# dedo_rev_1_0.net
KiCad netlist of a schematic drawn in EAGLE
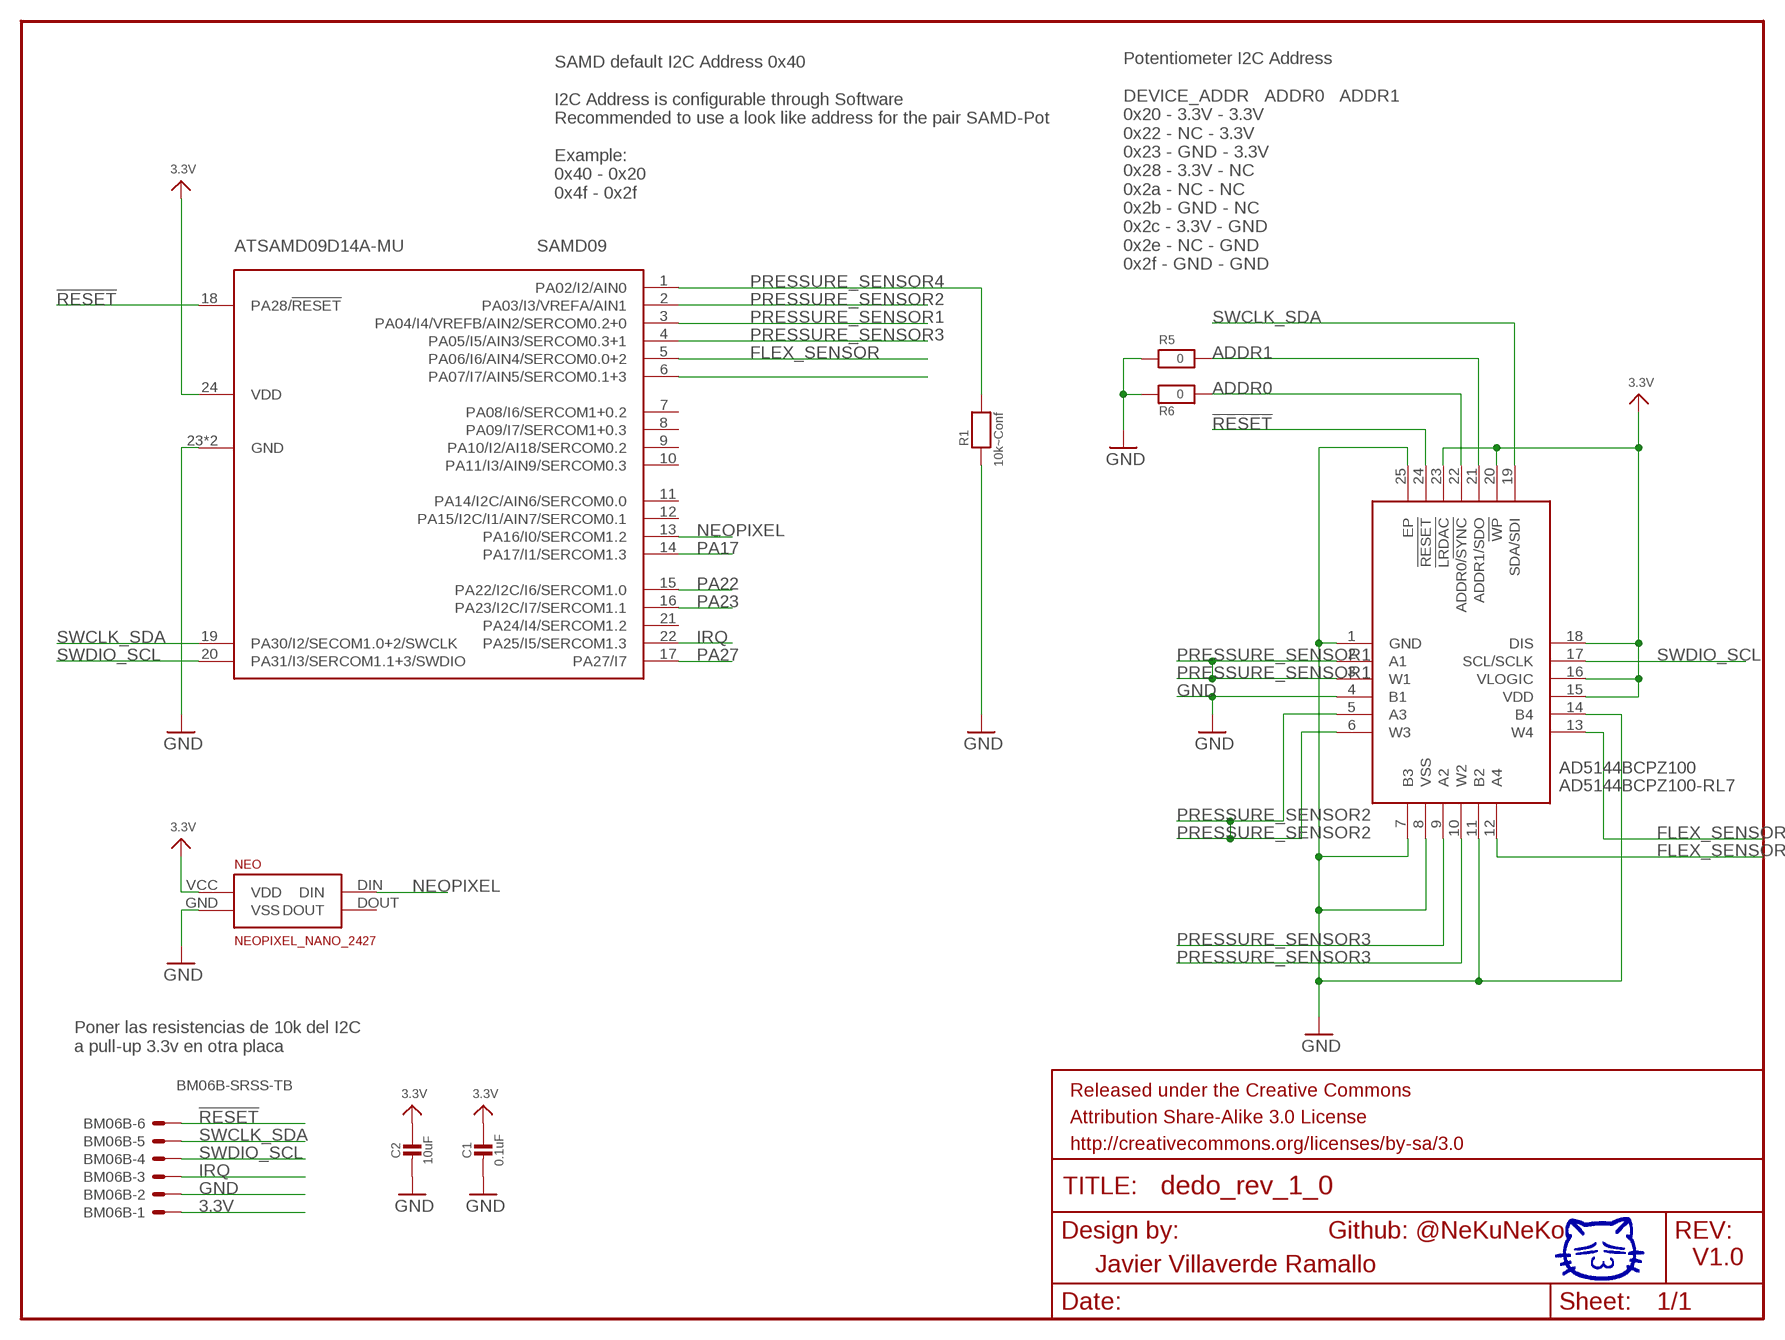
[diagram p0: schematic, sheet 1]

(export (version "E")
  (design (tool "Eeschema 10.0.6"))
  (components
    (comp (ref "AD5144BCPZ100")
      (value "AD5144BCPZ100-RL7")
      (footprint "eagle-import:QFN50P400X400X80-25N")
      (fields (field (name "MOUSER_PART_NUMBER") "584-AD5144BCPZ100-R7"))
      (libsource (lib "eagle-import") (part "AD5144BCPZ100-RL7"))
    )
    (comp (ref "BM06B")
      (value "BM06B-SRSS-TB")
      (footprint "eagle-import:BM06B-SRSS-TB")
      (libsource (lib "eagle-import") (part "?M06B-SRSS-TBB"))
    )
    (comp (ref "C1")
      (value "0.1uF")
      (footprint "eagle-import:0402")
      (libsource (lib "eagle-import") (part "CAP_CERAMIC0402"))
    )
    (comp (ref "C2")
      (value "10uF")
      (footprint "eagle-import:0402")
      (libsource (lib "eagle-import") (part "CAP_CERAMIC0402"))
    )
    (comp (ref "FRAME1")
      (value "FRAME-LETTER")
      (footprint "eagle-import:CREATIVE_COMMONS")
      (libsource (lib "eagle-import") (part "FRAME-LETTER"))
    )
    (comp (ref "FRAME2")
      (value "FRAME-LETTER")
      (footprint "eagle-import:CREATIVE_COMMONS")
      (libsource (lib "eagle-import") (part "FRAME-LETTER"))
    )
    (comp (ref "NEO")
      (value "NEOPIXEL_NANO_2427")
      (footprint "eagle-import:SK6805-2427")
      (libsource (lib "eagle-import") (part "NEOPIXEL_NANO_2427"))
    )
    (comp (ref "R1")
      (value "10k~Conf")
      (footprint "eagle-import:_0402")
      (libsource (lib "eagle-import") (part "RESISTOR_0402"))
    )
    (comp (ref "R5")
      (value "0")
      (footprint "eagle-import:_0402")
      (libsource (lib "eagle-import") (part "RESISTOR_0402"))
    )
    (comp (ref "R6")
      (value "0")
      (footprint "eagle-import:_0402")
      (libsource (lib "eagle-import") (part "RESISTOR_0402"))
    )
    (comp (ref "SAMD09")
      (value "ATSAMD09D14A-MU")
      (footprint "eagle-import:QFN24_4MM")
      (libsource (lib "eagle-import") (part "ATSAMD09D14A-MU"))
    )
  )
  (nets
    (net (code "1") (name "/ADDR0") (class "Default")
      (node (ref "AD5144BCPZ100") (pin "22") (pinfunction "ADDR0/~{SYNC}_22") (pintype "bidirectional"))
      (node (ref "R6") (pin "2") (pinfunction "2_2") (pintype "passive"))
    )
    (net (code "2") (name "/ADDR1") (class "Default")
      (node (ref "AD5144BCPZ100") (pin "21") (pinfunction "ADDR1/SDO_21") (pintype "bidirectional"))
      (node (ref "R5") (pin "2") (pinfunction "2_2") (pintype "passive"))
    )
    (net (code "3") (name "/FLEX_SENSOR") (class "Default")
      (node (ref "AD5144BCPZ100") (pin "12") (pinfunction "A4_12") (pintype "bidirectional"))
      (node (ref "AD5144BCPZ100") (pin "13") (pinfunction "W4_13") (pintype "bidirectional"))
      (node (ref "SAMD09") (pin "5") (pinfunction "PA06/I6/AIN4/SERCOM0.0+2_5") (pintype "bidirectional"))
    )
    (net (code "4") (name "/IRQ") (class "Default")
      (node (ref "BM06B") (pin "3") (pinfunction "S_3") (pintype "passive"))
      (node (ref "SAMD09") (pin "22") (pinfunction "PA25/I5/SERCOM1.3_22") (pintype "bidirectional"))
    )
    (net (code "5") (name "/NEOPIXEL") (class "Default")
      (node (ref "NEO") (pin "DIN") (pinfunction "DIN_DIN") (pintype "bidirectional"))
      (node (ref "SAMD09") (pin "13") (pinfunction "PA16/I0/SERCOM1.2_13") (pintype "bidirectional"))
    )
    (net (code "6") (name "/PA17") (class "Default")
      (node (ref "SAMD09") (pin "14") (pinfunction "PA17/I1/SERCOM1.3_14") (pintype "bidirectional"))
    )
    (net (code "7") (name "/PA22") (class "Default")
      (node (ref "SAMD09") (pin "15") (pinfunction "PA22/I2C/I6/SERCOM1.0_15") (pintype "bidirectional"))
    )
    (net (code "8") (name "/PA23") (class "Default")
      (node (ref "SAMD09") (pin "16") (pinfunction "PA23/I2C/I7/SERCOM1.1_16") (pintype "bidirectional"))
    )
    (net (code "9") (name "/PA27") (class "Default")
      (node (ref "SAMD09") (pin "17") (pinfunction "PA27/I7_17") (pintype "bidirectional"))
    )
    (net (code "10") (name "/PRESSURE_SENSOR1") (class "Default")
      (node (ref "AD5144BCPZ100") (pin "2") (pinfunction "A1_2") (pintype "bidirectional"))
      (node (ref "AD5144BCPZ100") (pin "3") (pinfunction "W1_3") (pintype "bidirectional"))
      (node (ref "SAMD09") (pin "3") (pinfunction "PA04/I4/VREFB/AIN2/SERCOM0.2+0_3") (pintype "bidirectional"))
    )
    (net (code "11") (name "/PRESSURE_SENSOR2") (class "Default")
      (node (ref "AD5144BCPZ100") (pin "5") (pinfunction "A3_5") (pintype "bidirectional"))
      (node (ref "AD5144BCPZ100") (pin "6") (pinfunction "W3_6") (pintype "bidirectional"))
      (node (ref "SAMD09") (pin "2") (pinfunction "PA03/I3/VREFA/AIN1_2") (pintype "bidirectional"))
    )
    (net (code "12") (name "/PRESSURE_SENSOR3") (class "Default")
      (node (ref "AD5144BCPZ100") (pin "10") (pinfunction "W2_10") (pintype "bidirectional"))
      (node (ref "AD5144BCPZ100") (pin "9") (pinfunction "A2_9") (pintype "bidirectional"))
      (node (ref "SAMD09") (pin "4") (pinfunction "PA05/I5/AIN3/SERCOM0.3+1_4") (pintype "bidirectional"))
    )
    (net (code "13") (name "/PRESSURE_SENSOR4") (class "Default")
      (node (ref "R1") (pin "1") (pinfunction "1_1") (pintype "passive"))
      (node (ref "SAMD09") (pin "1") (pinfunction "PA02/I2/AIN0_1") (pintype "bidirectional"))
    )
    (net (code "14") (name "/SWCLK_SDA") (class "Default")
      (node (ref "AD5144BCPZ100") (pin "19") (pinfunction "SDA/SDI_19") (pintype "bidirectional"))
      (node (ref "BM06B") (pin "5") (pinfunction "S_5") (pintype "passive"))
      (node (ref "SAMD09") (pin "19") (pinfunction "PA30/I2/SECOM1.0+2/SWCLK_19") (pintype "bidirectional"))
    )
    (net (code "15") (name "/SWDIO_SCL") (class "Default")
      (node (ref "AD5144BCPZ100") (pin "17") (pinfunction "SCL/SCLK_17") (pintype "bidirectional"))
      (node (ref "BM06B") (pin "4") (pinfunction "S_4") (pintype "passive"))
      (node (ref "SAMD09") (pin "20") (pinfunction "PA31/I3/SERCOM1.1+3/SWDIO_20") (pintype "bidirectional"))
    )
    (net (code "16") (name "/~{RESET}") (class "Default")
      (node (ref "AD5144BCPZ100") (pin "24") (pinfunction "~{RESET}_24") (pintype "bidirectional"))
      (node (ref "BM06B") (pin "6") (pinfunction "S_6") (pintype "passive"))
      (node (ref "SAMD09") (pin "18") (pinfunction "PA28/~{RESET}_18") (pintype "bidirectional"))
    )
    (net (code "17") (name "3.3V") (class "Default")
      (node (ref "AD5144BCPZ100") (pin "15") (pinfunction "VDD_15") (pintype "bidirectional"))
      (node (ref "AD5144BCPZ100") (pin "16") (pinfunction "VLOGIC_16") (pintype "bidirectional"))
      (node (ref "AD5144BCPZ100") (pin "18") (pinfunction "DIS_18") (pintype "bidirectional"))
      (node (ref "AD5144BCPZ100") (pin "20") (pinfunction "~{WP}_20") (pintype "bidirectional"))
      (node (ref "AD5144BCPZ100") (pin "23") (pinfunction "~{LRDAC}_23") (pintype "bidirectional"))
      (node (ref "BM06B") (pin "1") (pinfunction "S_1") (pintype "passive"))
      (node (ref "C1") (pin "1") (pinfunction "P$1_1") (pintype "passive"))
      (node (ref "C2") (pin "1") (pinfunction "P$1_1") (pintype "passive"))
      (node (ref "NEO") (pin "VCC") (pinfunction "VDD_VCC") (pintype "bidirectional"))
      (node (ref "SAMD09") (pin "24") (pinfunction "VDD_24") (pintype "power_in"))
    )
    (net (code "18") (name "GND") (class "Default")
      (node (ref "AD5144BCPZ100") (pin "1") (pinfunction "GND_1") (pintype "bidirectional"))
      (node (ref "AD5144BCPZ100") (pin "11") (pinfunction "B2_11") (pintype "bidirectional"))
      (node (ref "AD5144BCPZ100") (pin "14") (pinfunction "B4_14") (pintype "bidirectional"))
      (node (ref "AD5144BCPZ100") (pin "25") (pinfunction "EP_25") (pintype "bidirectional"))
      (node (ref "AD5144BCPZ100") (pin "4") (pinfunction "B1_4") (pintype "bidirectional"))
      (node (ref "AD5144BCPZ100") (pin "7") (pinfunction "B3_7") (pintype "bidirectional"))
      (node (ref "AD5144BCPZ100") (pin "8") (pinfunction "VSS_8") (pintype "bidirectional"))
      (node (ref "BM06B") (pin "2") (pinfunction "S_2") (pintype "passive"))
      (node (ref "C1") (pin "2") (pinfunction "P$2_2") (pintype "passive"))
      (node (ref "C2") (pin "2") (pinfunction "P$2_2") (pintype "passive"))
      (node (ref "NEO") (pin "GND") (pinfunction "VSS_GND") (pintype "bidirectional"))
      (node (ref "R1") (pin "2") (pinfunction "2_2") (pintype "passive"))
      (node (ref "R5") (pin "1") (pinfunction "1_1") (pintype "passive"))
      (node (ref "R6") (pin "1") (pinfunction "1_1") (pintype "passive"))
      (node (ref "SAMD09") (pin "23") (pinfunction "GND_23") (pintype "power_in"))
      (node (ref "SAMD09") (pin "THERM") (pinfunction "GND_THERM") (pintype "power_in"))
    )
    (net (code "19") (name "unconnected-(NEO-PadDOUT)") (class "Default")
      (node (ref "NEO") (pin "DOUT") (pinfunction "DOUT_DOUT") (pintype "bidirectional"))
    )
    (net (code "20") (name "unconnected-(SAMD09-PA07{slash}I7{slash}AIN5{slash}SERCOM0.1+3-Pad6)") (class "Default")
      (node (ref "SAMD09") (pin "6") (pinfunction "PA07/I7/AIN5/SERCOM0.1+3_6") (pintype "bidirectional"))
    )
    (net (code "21") (name "unconnected-(SAMD09-PA08{slash}I6{slash}SERCOM1+0.2-Pad7)") (class "Default")
      (node (ref "SAMD09") (pin "7") (pinfunction "PA08/I6/SERCOM1+0.2_7") (pintype "bidirectional"))
    )
    (net (code "22") (name "unconnected-(SAMD09-PA09{slash}I7{slash}SERCOM1+0.3-Pad8)") (class "Default")
      (node (ref "SAMD09") (pin "8") (pinfunction "PA09/I7/SERCOM1+0.3_8") (pintype "bidirectional"))
    )
    (net (code "23") (name "unconnected-(SAMD09-PA10{slash}I2{slash}AI18{slash}SERCOM0.2-Pad9)") (class "Default")
      (node (ref "SAMD09") (pin "9") (pinfunction "PA10/I2/AI18/SERCOM0.2_9") (pintype "bidirectional"))
    )
    (net (code "24") (name "unconnected-(SAMD09-PA11{slash}I3{slash}AIN9{slash}SERCOM0.3-Pad10)") (class "Default")
      (node (ref "SAMD09") (pin "10") (pinfunction "PA11/I3/AIN9/SERCOM0.3_10") (pintype "bidirectional"))
    )
    (net (code "25") (name "unconnected-(SAMD09-PA14{slash}I2C{slash}AIN6{slash}SERCOM0.0-Pad11)") (class "Default")
      (node (ref "SAMD09") (pin "11") (pinfunction "PA14/I2C/AIN6/SERCOM0.0_11") (pintype "bidirectional"))
    )
    (net (code "26") (name "unconnected-(SAMD09-PA15{slash}I2C{slash}I1{slash}AIN7{slash}SERCOM0.1-Pad12)") (class "Default")
      (node (ref "SAMD09") (pin "12") (pinfunction "PA15/I2C/I1/AIN7/SERCOM0.1_12") (pintype "bidirectional"))
    )
    (net (code "27") (name "unconnected-(SAMD09-PA24{slash}I4{slash}SERCOM1.2-Pad21)") (class "Default")
      (node (ref "SAMD09") (pin "21") (pinfunction "PA24/I4/SERCOM1.2_21") (pintype "bidirectional"))
    )
  )
)
